# Stepper_Driver.net
KiCad netlist of a schematic drawn in Altium Designer
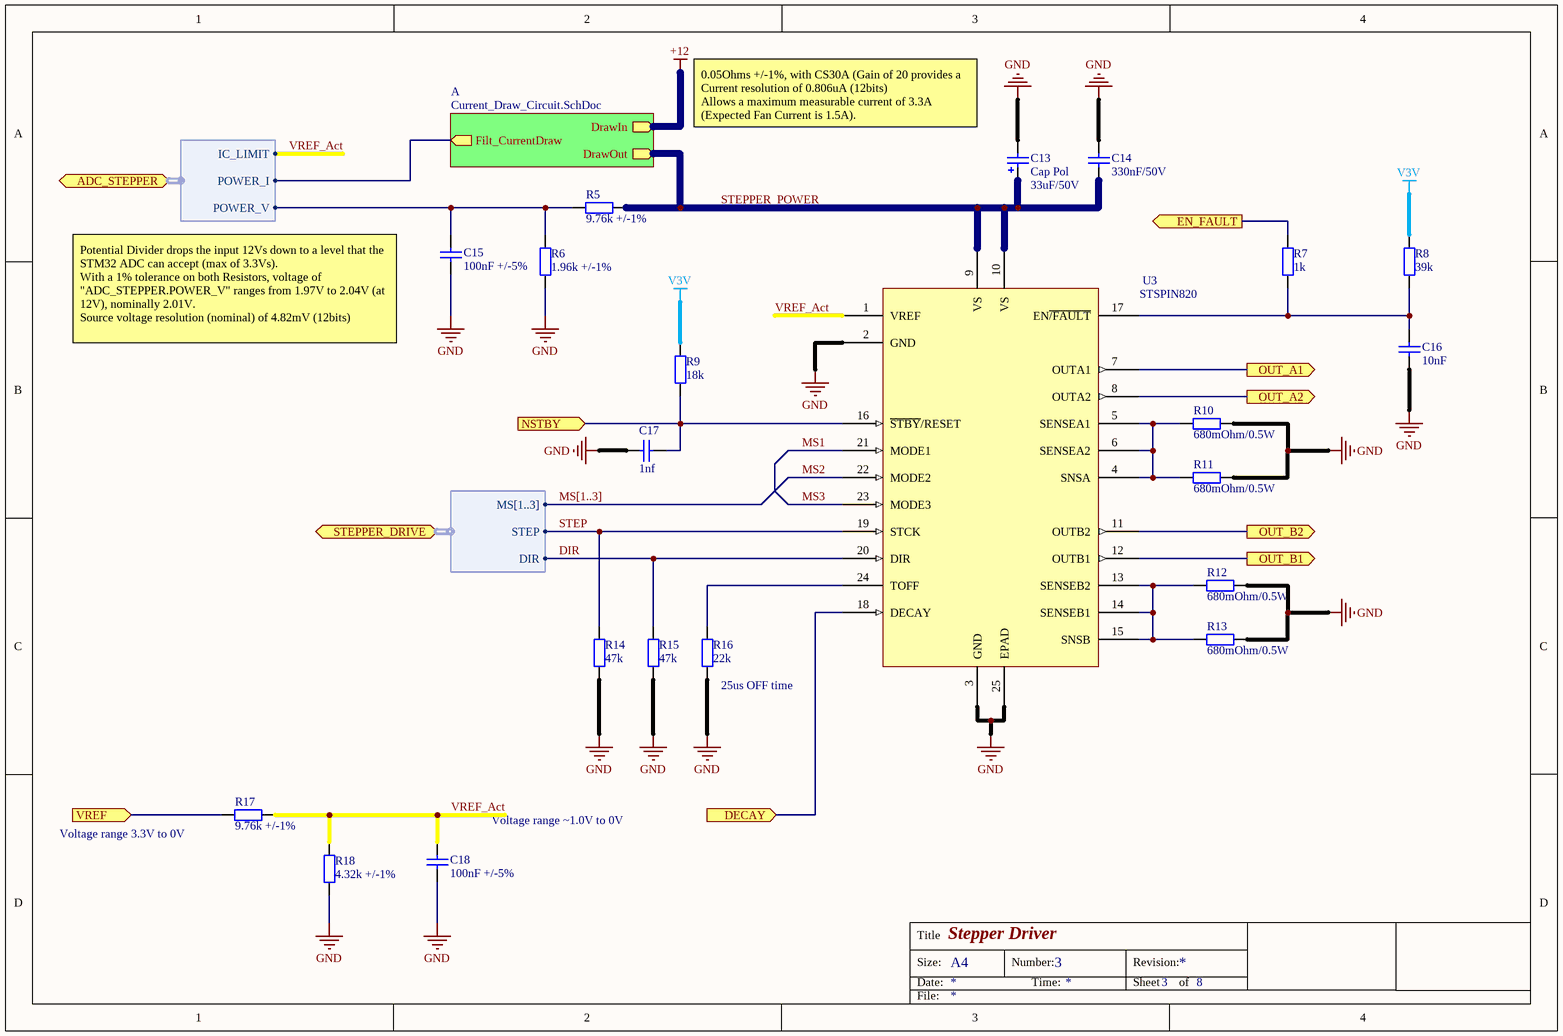
[diagram p0: Stepper_Driver.SchDoc]

(export (version "E")
  (design (tool "Eeschema 10.0.6"))
  (components
    (comp (ref "C13")
      (value "Cap Pol")
      (footprint "CAPAE7066X77M")
      (description "Polarized Capacitor (Surface Mount)")
      (fields (field (name "ALTIUM_VALUE") "33uF/50V") (field (name "PUBLISHER") "Altium Limited"))
      (libsource (lib "miStepper_SchematicLib") (part "Cap Pol"))
    )
    (comp (ref "C14")
      (value "330nF/50V")
      (footprint "CAPC3216X06N (1206)")
      (description "Capacitor (Semiconductor SIM Model)")
      (fields (field (name "Comment") "Cap Semi") (field (name "PUBLISHER") "Altium Limited"))
      (libsource (lib "miStepper_SchematicLib") (part "Cap Semi"))
    )
    (comp (ref "C15")
      (value "100nF +/-5%")
      (footprint "CAPC1608X06N (0603)")
      (description "Capacitor (Semiconductor SIM Model)")
      (fields (field (name "Comment") "Cap Semi") (field (name "PUBLISHER") "Altium Limited"))
      (libsource (lib "miStepper_SchematicLib") (part "Cap Semi"))
    )
    (comp (ref "C16")
      (value "10nF")
      (footprint "CAPC1608X06N (0603)")
      (description "Capacitor (Semiconductor SIM Model)")
      (fields (field (name "Comment") "Cap Semi") (field (name "PUBLISHER") "Altium Limited"))
      (libsource (lib "miStepper_SchematicLib") (part "Cap Semi"))
    )
    (comp (ref "C17")
      (value "1nf")
      (footprint "CAPC1608X06N (0603)")
      (description "Capacitor (Semiconductor SIM Model)")
      (fields (field (name "Comment") "Cap Semi") (field (name "PUBLISHER") "Altium Limited"))
      (libsource (lib "miStepper_SchematicLib") (part "Cap Semi"))
    )
    (comp (ref "C18")
      (value "100nF +/-5%")
      (footprint "CAPC1608X06N (0603)")
      (description "Capacitor (Semiconductor SIM Model)")
      (fields (field (name "Comment") "Cap Semi") (field (name "PUBLISHER") "Altium Limited"))
      (libsource (lib "miStepper_SchematicLib") (part "Cap Semi"))
    )
    (comp (ref "R5")
      (value "9.76k +/-1%")
      (footprint "RESC1608X06N (0603)")
      (description "Resistor")
      (fields (field (name "Comment") "Res") (field (name "PUBLISHER") "Altium Limited"))
      (libsource (lib "miStepper_SchematicLib") (part "Res"))
    )
    (comp (ref "R6")
      (value "1.96k +/-1%")
      (footprint "RESC1608X06N (0603)")
      (description "Resistor")
      (fields (field (name "Comment") "Res") (field (name "PUBLISHER") "Altium Limited"))
      (libsource (lib "") (part "Res_1"))
    )
    (comp (ref "R7")
      (value "1k")
      (footprint "RESC1608X06N (0603)")
      (description "Resistor")
      (fields (field (name "Comment") "Res") (field (name "PUBLISHER") "Altium Limited"))
      (libsource (lib "") (part "Res_1"))
    )
    (comp (ref "R8")
      (value "39k")
      (footprint "RESC1608X06N (0603)")
      (description "Resistor")
      (fields (field (name "Comment") "Res") (field (name "PUBLISHER") "Altium Limited"))
      (libsource (lib "") (part "Res_1"))
    )
    (comp (ref "R9")
      (value "18k")
      (footprint "RESC1608X06N (0603)")
      (description "Resistor")
      (fields (field (name "Comment") "Res") (field (name "PUBLISHER") "Altium Limited"))
      (libsource (lib "") (part "Res_1"))
    )
    (comp (ref "R10")
      (value "680mOhm/0.5W")
      (footprint "RESC2012X06N (0805)")
      (description "Resistor")
      (fields (field (name "Comment") "Res") (field (name "PUBLISHER") "Altium Limited"))
      (libsource (lib "miStepper_SchematicLib") (part "Res"))
    )
    (comp (ref "R11")
      (value "680mOhm/0.5W")
      (footprint "RESC2012X06N (0805)")
      (description "Resistor")
      (fields (field (name "Comment") "Res") (field (name "PUBLISHER") "Altium Limited"))
      (libsource (lib "miStepper_SchematicLib") (part "Res"))
    )
    (comp (ref "R12")
      (value "680mOhm/0.5W")
      (footprint "RESC2012X06N (0805)")
      (description "Resistor")
      (fields (field (name "Comment") "Res") (field (name "PUBLISHER") "Altium Limited"))
      (libsource (lib "miStepper_SchematicLib") (part "Res"))
    )
    (comp (ref "R13")
      (value "680mOhm/0.5W")
      (footprint "RESC2012X06N (0805)")
      (description "Resistor")
      (fields (field (name "Comment") "Res") (field (name "PUBLISHER") "Altium Limited"))
      (libsource (lib "miStepper_SchematicLib") (part "Res"))
    )
    (comp (ref "R14")
      (value "47k")
      (footprint "RESC1608X06N (0603)")
      (description "Resistor")
      (fields (field (name "Comment") "Res") (field (name "PUBLISHER") "Altium Limited"))
      (libsource (lib "") (part "Res_2"))
    )
    (comp (ref "R15")
      (value "47k")
      (footprint "RESC1608X06N (0603)")
      (description "Resistor")
      (fields (field (name "Comment") "Res") (field (name "PUBLISHER") "Altium Limited"))
      (libsource (lib "") (part "Res_2"))
    )
    (comp (ref "R16")
      (value "22k")
      (footprint "RESC1608X06N (0603)")
      (description "Resistor")
      (fields (field (name "Comment") "Res") (field (name "PUBLISHER") "Altium Limited"))
      (libsource (lib "") (part "Res_2"))
    )
    (comp (ref "R17")
      (value "9.76k +/-1%")
      (footprint "RESC1608X06N (0603)")
      (description "Resistor")
      (fields (field (name "Comment") "Res") (field (name "PUBLISHER") "Altium Limited"))
      (libsource (lib "miStepper_SchematicLib") (part "Res"))
    )
    (comp (ref "R18")
      (value "4.32k +/-1%")
      (footprint "RESC1608X06N (0603)")
      (description "Resistor")
      (fields (field (name "Comment") "Res") (field (name "PUBLISHER") "Altium Limited"))
      (libsource (lib "") (part "Res_1"))
    )
    (comp (ref "U3")
      (value "STSPIN820")
      (footprint "QFN50P400X400X110-25N")
      (description "Stepper IC")
      (libsource (lib "miStepper_SchematicLib") (part "STSPIN820"))
    )
  )
  (nets
    (net (code "4") (name "/DECAY") (class "Default")
      (node (ref "U3") (pin "18") (pinfunction "DECAY_18") (pintype "input"))
    )
    (net (code "5") (name "/DIR") (class "Default")
      (node (ref "R15") (pin "1") (pinfunction "1_1") (pintype "passive"))
      (node (ref "U3") (pin "20") (pinfunction "DIR_20") (pintype "input"))
    )
    (net (code "6") (name "/EN_FAULT") (class "Default")
      (node (ref "R7") (pin "2") (pinfunction "2_2") (pintype "passive"))
    )
    (net (code "8") (name "/MS1") (class "Default")
      (node (ref "U3") (pin "21") (pinfunction "MODE1_21") (pintype "input"))
    )
    (net (code "9") (name "/MS2") (class "Default")
      (node (ref "U3") (pin "22") (pinfunction "MODE2_22") (pintype "input"))
    )
    (net (code "10") (name "/MS3") (class "Default")
      (node (ref "U3") (pin "23") (pinfunction "MODE3_23") (pintype "input"))
    )
    (net (code "12") (name "/NSTBY") (class "Default")
      (node (ref "C17") (pin "1") (pinfunction "1_1") (pintype "passive"))
      (node (ref "R9") (pin "1") (pinfunction "1_1") (pintype "passive"))
      (node (ref "U3") (pin "16") (pinfunction "~{STBY}/RESET_16") (pintype "input"))
    )
    (net (code "13") (name "/OUT_A1") (class "Default")
      (node (ref "U3") (pin "7") (pinfunction "OUTA1_7") (pintype "output"))
    )
    (net (code "14") (name "/OUT_A2") (class "Default")
      (node (ref "U3") (pin "8") (pinfunction "OUTA2_8") (pintype "output"))
    )
    (net (code "15") (name "/OUT_B1") (class "Default")
      (node (ref "U3") (pin "12") (pinfunction "OUTB1_12") (pintype "output"))
    )
    (net (code "16") (name "/OUT_B2") (class "Default")
      (node (ref "U3") (pin "11") (pinfunction "OUTB2_11") (pintype "output"))
    )
    (net (code "17") (name "/STEP") (class "Default")
      (node (ref "R14") (pin "1") (pinfunction "1_1") (pintype "passive"))
      (node (ref "U3") (pin "19") (pinfunction "STCK_19") (pintype "input"))
    )
    (net (code "18") (name "/STEPPER_POWER") (class "Default")
      (node (ref "C13") (pin "1") (pinfunction "1_1") (pintype "passive"))
      (node (ref "C14") (pin "2") (pinfunction "2_2") (pintype "passive"))
      (node (ref "R5") (pin "2") (pinfunction "2_2") (pintype "passive"))
      (node (ref "U3") (pin "10") (pinfunction "VS_10") (pintype "power_in"))
      (node (ref "U3") (pin "9") (pinfunction "VS_9") (pintype "power_in"))
    )
    (net (code "19") (name "/VREF") (class "Default")
      (node (ref "R17") (pin "1") (pinfunction "1_1") (pintype "passive"))
    )
    (net (code "20") (name "/VREF_Act") (class "Default")
      (node (ref "C18") (pin "2") (pinfunction "2_2") (pintype "passive"))
      (node (ref "R17") (pin "2") (pinfunction "2_2") (pintype "passive"))
      (node (ref "R18") (pin "2") (pinfunction "2_2") (pintype "passive"))
      (node (ref "U3") (pin "1") (pinfunction "VREF_1") (pintype "passive"))
    )
    (net (code "23") (name "GND") (class "Default")
      (node (ref "C13") (pin "2") (pinfunction "2_2") (pintype "passive"))
      (node (ref "C14") (pin "1") (pinfunction "1_1") (pintype "passive"))
      (node (ref "C15") (pin "1") (pinfunction "1_1") (pintype "passive"))
      (node (ref "C16") (pin "2") (pinfunction "2_2") (pintype "passive"))
      (node (ref "C17") (pin "2") (pinfunction "2_2") (pintype "passive"))
      (node (ref "C18") (pin "1") (pinfunction "1_1") (pintype "passive"))
      (node (ref "R10") (pin "2") (pinfunction "2_2") (pintype "passive"))
      (node (ref "R11") (pin "2") (pinfunction "2_2") (pintype "passive"))
      (node (ref "R12") (pin "2") (pinfunction "2_2") (pintype "passive"))
      (node (ref "R13") (pin "2") (pinfunction "2_2") (pintype "passive"))
      (node (ref "R14") (pin "2") (pinfunction "2_2") (pintype "passive"))
      (node (ref "R15") (pin "2") (pinfunction "2_2") (pintype "passive"))
      (node (ref "R16") (pin "2") (pinfunction "2_2") (pintype "passive"))
      (node (ref "R18") (pin "1") (pinfunction "1_1") (pintype "passive"))
      (node (ref "R6") (pin "1") (pinfunction "1_1") (pintype "passive"))
      (node (ref "U3") (pin "2") (pinfunction "GND_2") (pintype "power_in"))
      (node (ref "U3") (pin "25") (pinfunction "EPAD_25") (pintype "power_in"))
      (node (ref "U3") (pin "3") (pinfunction "GND_3") (pintype "power_in"))
    )
    (net (code "24") (name "Net-(C15-Pad2)") (class "Default")
      (node (ref "C15") (pin "2") (pinfunction "2_2") (pintype "passive"))
      (node (ref "R5") (pin "1") (pinfunction "1_1") (pintype "passive"))
      (node (ref "R6") (pin "2") (pinfunction "2_2") (pintype "passive"))
    )
    (net (code "25") (name "Net-(U3-EN~{{slash}FAULT})") (class "Default")
      (node (ref "C16") (pin "1") (pinfunction "1_1") (pintype "passive"))
      (node (ref "R7") (pin "1") (pinfunction "1_1") (pintype "passive"))
      (node (ref "R8") (pin "1") (pinfunction "1_1") (pintype "passive"))
      (node (ref "U3") (pin "17") (pinfunction "EN~{/FAULT}_17") (pintype "passive"))
    )
    (net (code "26") (name "Net-(U3-SENSEA1)") (class "Default")
      (node (ref "R10") (pin "1") (pinfunction "1_1") (pintype "passive"))
      (node (ref "R11") (pin "1") (pinfunction "1_1") (pintype "passive"))
      (node (ref "U3") (pin "4") (pinfunction "SNSA_4") (pintype "passive"))
      (node (ref "U3") (pin "5") (pinfunction "SENSEA1_5") (pintype "passive"))
      (node (ref "U3") (pin "6") (pinfunction "SENSEA2_6") (pintype "passive"))
    )
    (net (code "27") (name "Net-(U3-SENSEB1)") (class "Default")
      (node (ref "R12") (pin "1") (pinfunction "1_1") (pintype "passive"))
      (node (ref "R13") (pin "1") (pinfunction "1_1") (pintype "passive"))
      (node (ref "U3") (pin "13") (pinfunction "SENSEB2_13") (pintype "passive"))
      (node (ref "U3") (pin "14") (pinfunction "SENSEB1_14") (pintype "passive"))
      (node (ref "U3") (pin "15") (pinfunction "SNSB_15") (pintype "passive"))
    )
    (net (code "28") (name "Net-(U3-TOFF)") (class "Default")
      (node (ref "R16") (pin "1") (pinfunction "1_1") (pintype "passive"))
      (node (ref "U3") (pin "24") (pinfunction "TOFF_24") (pintype "passive"))
    )
    (net (code "29") (name "V3V") (class "Default")
      (node (ref "R8") (pin "2") (pinfunction "2_2") (pintype "passive"))
      (node (ref "R9") (pin "2") (pinfunction "2_2") (pintype "passive"))
    )
  )
)
